# 3_-_STM32f4_debuger.net
KiCad netlist of a schematic drawn in Altium Designer
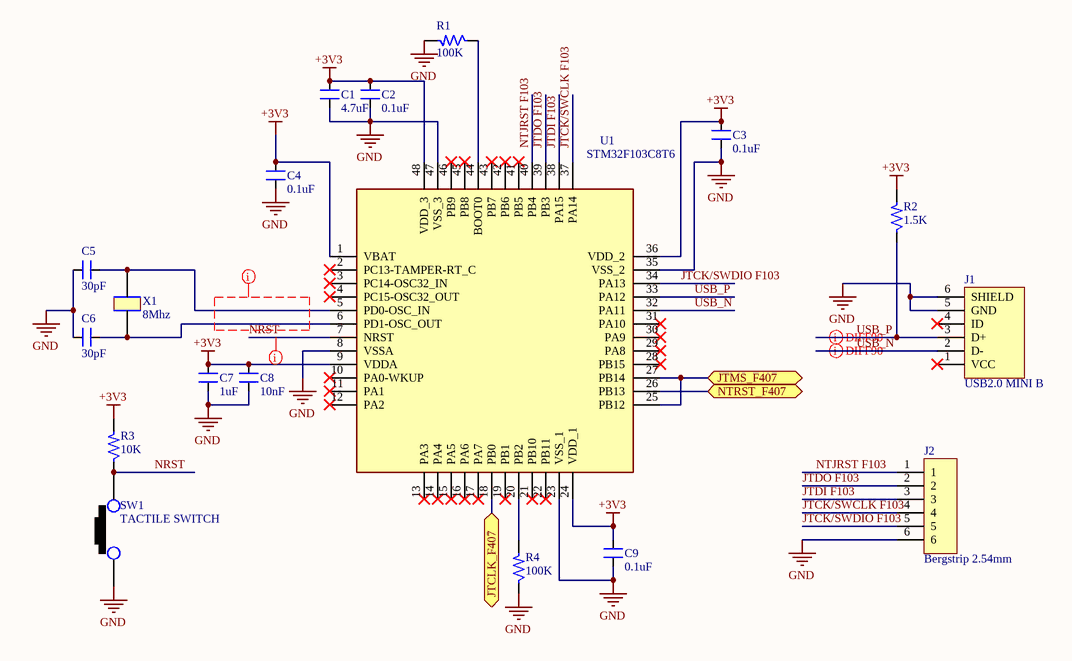
[diagram p0: [3]- STM32f4 debuger.SchDoc]

(export (version "E")
  (design (tool "Eeschema 10.0.6"))
  (components
    (comp (ref "C1")
      (value "4.7uF")
      (footprint "CAP_0805")
      (description "4.7µF ±10% 50V Ceramic Capacitor X5R 0805 (2012 Metric)")
      (fields
        (field (name "MANUFACTURER") "Yageo")
        (field (name "MANUFACTURER PART NUMBER") "GRM21BR61H475KE51L")
      )
      (libsource (lib "ESTEEMPCBLIB") (part "CAP_4.7uF-50V-10%-0805"))
    )
    (comp (ref "C2")
      (value "0.1uF")
      (footprint "CAP_0805")
      (description "0.1µF ±10% 50V Ceramic Capacitor X7R 0805 (2012 Metric)")
      (fields
        (field (name "MANUFACTURER") "Samsung")
        (field (name "MANUFACTURER PART NUMBER") "CL21B104KBCNNNC")
      )
      (libsource (lib "ESTEEMPCBLIB") (part "CAP_0.1uF-50V-10%-0805"))
    )
    (comp (ref "C3")
      (value "0.1uF")
      (footprint "CAP_0805")
      (description "0.1µF ±10% 50V Ceramic Capacitor X7R 0805 (2012 Metric)")
      (fields
        (field (name "MANUFACTURER") "Samsung")
        (field (name "MANUFACTURER PART NUMBER") "CL21B104KBCNNNC")
      )
      (libsource (lib "ESTEEMPCBLIB") (part "CAP_0.1uF-50V-10%-0805"))
    )
    (comp (ref "C4")
      (value "0.1uF")
      (footprint "CAP_0805")
      (description "0.1µF ±10% 50V Ceramic Capacitor X7R 0805 (2012 Metric)")
      (fields
        (field (name "MANUFACTURER") "Samsung")
        (field (name "MANUFACTURER PART NUMBER") "CL21B104KBCNNNC")
      )
      (libsource (lib "ESTEEMPCBLIB") (part "CAP_0.1uF-50V-10%-0805"))
    )
    (comp (ref "C5")
      (value "30pF")
      (footprint "CAP_0805")
      (description "±10% 50V Ceramic Capacitor C0G, NP0 0805 (2012 Metric)")
      (fields
        (field (name "MANUFACTURER PART NUMBER") "C0805C300K5GAC7800")
        (field (name "MANUFACTURER") "KEMET")
      )
      (libsource (lib "ESTEEMPCBLIB") (part "CAP_30pF-50V-10%-0805"))
    )
    (comp (ref "C6")
      (value "30pF")
      (footprint "CAP_0805")
      (description "±10% 50V Ceramic Capacitor C0G, NP0 0805 (2012 Metric)")
      (fields
        (field (name "MANUFACTURER PART NUMBER") "C0805C300K5GAC7800")
        (field (name "MANUFACTURER") "KEMET")
      )
      (libsource (lib "ESTEEMPCBLIB") (part "CAP_30pF-50V-10%-0805"))
    )
    (comp (ref "C7")
      (value "1uF")
      (footprint "CAP_0805")
      (description "1µF ±5% 50V Ceramic Capacitor X7R 0805 (2012 Metric)")
      (fields
        (field (name "MANUFACTURER") "Samsung")
        (field (name "MANUFACTURER PART NUMBER") "CC0805JKX7R9BB105")
      )
      (libsource (lib "ESTEEMPCBLIB") (part "CAP_1uF-50V-5%-0805"))
    )
    (comp (ref "C8")
      (value "10nF")
      (footprint "CAP_0805")
      (description "10000pF ±10% 50V Ceramic Capacitor X7R 0805 (2012 Metric)")
      (fields
        (field (name "MANUFACTURER") "Samsung")
        (field (name "MANUFACTURER PART NUMBER") "C0805C103K5RECAUTO")
      )
      (libsource (lib "ESTEEMPCBLIB") (part "CAP_10nF-50V-10%-0805"))
    )
    (comp (ref "C9")
      (value "0.1uF")
      (footprint "CAP_0805")
      (description "0.1µF ±10% 50V Ceramic Capacitor X7R 0805 (2012 Metric)")
      (fields
        (field (name "MANUFACTURER") "Samsung")
        (field (name "MANUFACTURER PART NUMBER") "CL21B104KBCNNNC")
      )
      (libsource (lib "ESTEEMPCBLIB") (part "CAP_0.1uF-50V-10%-0805"))
    )
    (comp (ref "J1")
      (value "USB2.0 MINI B")
      (footprint "CON_690-005-299-043")
      (description "USB - mini B USB 2.0 Receptacle Connector 5 Position Surface Mount, Right Angle")
      (fields
        (field (name "MANUFACTURER") "EDAC")
        (field (name "MANUFACTURER PART NUMBER") "690-005-299-043")
      )
      (libsource (lib "ESTEEMPCBLIB") (part "CON_USB2.0-MINIB-SMD"))
    )
    (comp (ref "J2")
      (value "Bergstrip 2.54mm")
      (footprint "CON6_100_59D78_TH_ST")
      (description "6 Pins, 1 Row 2.54mm Pitch, Straight bergstrip, Female")
      (fields (field (name "MANUFACTURER") "Molex") (field (name "MANUFACTURER PART NUMBER") "22-10-2061"))
      (libsource (lib "ESTEEMPCBLIB") (part "CON-BS-SKT_6X1-100-ST-TH"))
    )
    (comp (ref "R1")
      (value "100K")
      (footprint "RES_0603")
      (description "100 kOhms ±1% 0.1W, 1/10W Chip Resistor 0603 (1608 Metric) Automotive AEC-Q200 Thick Film")
      (fields
        (field (name "MANUFACTURER") "Stackpole Electronics")
        (field (name "MANUFACTURER PART NUMBER") "RMCF0603FT100K")
      )
      (libsource (lib "ESTEEMPCBLIB") (part "RES_100K-0.1W-1%-0603"))
    )
    (comp (ref "R2")
      (value "1.5K")
      (footprint "RES_0805")
      (description "1.5 kOhms ±1% 0.125W, 1/8W Chip Resistor 0805 (2012 Metric) Thick Film")
      (fields
        (field (name "MANUFACTURER") "TE Connectivity Passive Product")
        (field (name "MANUFACTURER PART NUMBER") "CRG0805F1K5")
      )
      (libsource (lib "ESTEEMPCBLIB") (part "RES_1.5K-0.125W-1%-0805"))
    )
    (comp (ref "R3")
      (value "10K")
      (footprint "RES_0603")
      (description "10 kOhms ±1% 0.1W, 1/10W Chip Resistor 0603 (1608 Metric) Automotive AEC-Q200 Thick Film")
      (fields (field (name "MANUFACTURER") "Walsin") (field (name "MANUFACTURER PART NUMBER") "WR06X1002FTL"))
      (libsource (lib "ESTEEMPCBLIB") (part "RES_10K-0.1W-1%-0603"))
    )
    (comp (ref "R4")
      (value "100K")
      (footprint "RES_0603")
      (description "100 kOhms ±1% 0.1W, 1/10W Chip Resistor 0603 (1608 Metric) Automotive AEC-Q200 Thick Film")
      (fields
        (field (name "MANUFACTURER") "Stackpole Electronics")
        (field (name "MANUFACTURER PART NUMBER") "RMCF0603FT100K")
      )
      (libsource (lib "ESTEEMPCBLIB") (part "RES_100K-0.1W-1%-0603"))
    )
    (comp (ref "SW1")
      (value "TACTILE SWITCH")
      (footprint "SW_342_SMD")
      (description "Tactile Switch SPST-NO Top Actuated Surface Mount")
      (fields
        (field (name "MANUFACTURER") "ITT C&K")
        (field (name "MANUFACTURER PART NUMBER") "RS-282G05A3-SMRT")
      )
      (libsource (lib "ESTEEMPCBLIB") (part "SW1_RS-282G05A3-SMRT-SMD"))
    )
    (comp (ref "U1")
      (value "STM32F103C8T6")
      (footprint "LQFP-48_19.6_393_58X11_SMD")
      (description "ARM® Cortex®-M3 STM32F1 Microcontroller IC 32-Bit 72MHz 64KB (64K x 8) FLASH 48-LQFP (7x7)")
      (fields (field (name "MANUFACTURER") "STMicroelectronics"))
      (libsource (lib "ESTEEMPCBLIB") (part "IC_STM32F103C8T6"))
    )
    (comp (ref "X1")
      (value "8Mhz")
      (footprint "XTAL_314_240X47_SMD")
      (description "8MHz ±30ppm Crystal 32pF 60 Ohms HC-49/US")
      (fields
        (field (name "MANUFACTURER") "Fox Electronics")
        (field (name "MANUFACTURER PART NUMBER") "ECS-80-32-5PX-TR")
      )
      (libsource (lib "ESTEEMPCBLIB") (part "XTAL_8MHZ-ECS-80-32-5PX-SMD"))
    )
  )
  (nets
    (net (code "1") (name "+3V3") (class "Default")
      (node (ref "C1") (pin "2") (pinfunction "2_2") (pintype "passive"))
      (node (ref "C2") (pin "2") (pinfunction "2_2") (pintype "passive"))
      (node (ref "C3") (pin "2") (pinfunction "2_2") (pintype "passive"))
      (node (ref "C4") (pin "2") (pinfunction "2_2") (pintype "passive"))
      (node (ref "C7") (pin "2") (pinfunction "2_2") (pintype "passive"))
      (node (ref "C8") (pin "2") (pinfunction "2_2") (pintype "passive"))
      (node (ref "C9") (pin "2") (pinfunction "2_2") (pintype "passive"))
      (node (ref "R2") (pin "2") (pinfunction "2_2") (pintype "passive"))
      (node (ref "R3") (pin "2") (pinfunction "2_2") (pintype "passive"))
      (node (ref "U1") (pin "1") (pinfunction "VBAT_1") (pintype "passive"))
      (node (ref "U1") (pin "24") (pinfunction "VDD_1_24") (pintype "passive"))
      (node (ref "U1") (pin "36") (pinfunction "VDD_2_36") (pintype "passive"))
      (node (ref "U1") (pin "48") (pinfunction "VDD_3_48") (pintype "passive"))
      (node (ref "U1") (pin "9") (pinfunction "VDDA_9") (pintype "passive"))
    )
    (net (code "2") (name "/JTCK{slash}SWCLK F103") (class "Default")
      (node (ref "J2") (pin "4") (pinfunction "4_4") (pintype "passive"))
      (node (ref "U1") (pin "37") (pinfunction "PA14_37") (pintype "passive"))
    )
    (net (code "3") (name "/JTCK{slash}SWDIO F103") (class "Default")
      (node (ref "J2") (pin "5") (pinfunction "5_5") (pintype "passive"))
      (node (ref "U1") (pin "34") (pinfunction "PA13_34") (pintype "passive"))
    )
    (net (code "4") (name "/JTCLK_F407") (class "Default")
      (node (ref "U1") (pin "18") (pinfunction "PB0_18") (pintype "passive"))
    )
    (net (code "5") (name "/JTDI F103") (class "Default")
      (node (ref "J2") (pin "3") (pinfunction "3_3") (pintype "passive"))
      (node (ref "U1") (pin "38") (pinfunction "PA15_38") (pintype "passive"))
    )
    (net (code "6") (name "/JTDO F103") (class "Default")
      (node (ref "J2") (pin "2") (pinfunction "2_2") (pintype "passive"))
      (node (ref "U1") (pin "39") (pinfunction "PB3_39") (pintype "passive"))
    )
    (net (code "7") (name "/JTMS_F407") (class "Default")
      (node (ref "U1") (pin "25") (pinfunction "PB12_25") (pintype "passive"))
      (node (ref "U1") (pin "27") (pinfunction "PB14_27") (pintype "passive"))
    )
    (net (code "8") (name "/NRST") (class "Default")
      (node (ref "R3") (pin "1") (pinfunction "1_1") (pintype "passive"))
      (node (ref "SW1") (pin "2") (pinfunction "2_2") (pintype "passive"))
      (node (ref "U1") (pin "7") (pinfunction "NRST_7") (pintype "passive"))
    )
    (net (code "9") (name "/NTJRST F103") (class "Default")
      (node (ref "J2") (pin "1") (pinfunction "1_1") (pintype "passive"))
      (node (ref "U1") (pin "40") (pinfunction "PB4_40") (pintype "passive"))
    )
    (net (code "10") (name "/NTRST_F407") (class "Default")
      (node (ref "U1") (pin "26") (pinfunction "PB13_26") (pintype "passive"))
    )
    (net (code "11") (name "/USB_N") (class "Default")
      (node (ref "J1") (pin "2") (pinfunction "D-_2") (pintype "passive"))
      (node (ref "U1") (pin "32") (pinfunction "PA11_32") (pintype "passive"))
    )
    (net (code "12") (name "/USB_P") (class "Default")
      (node (ref "J1") (pin "3") (pinfunction "D+_3") (pintype "passive"))
      (node (ref "R2") (pin "1") (pinfunction "1_1") (pintype "passive"))
      (node (ref "U1") (pin "33") (pinfunction "PA12_33") (pintype "passive"))
    )
    (net (code "13") (name "GND") (class "Default")
      (node (ref "C1") (pin "1") (pinfunction "1_1") (pintype "passive"))
      (node (ref "C2") (pin "1") (pinfunction "1_1") (pintype "passive"))
      (node (ref "C3") (pin "1") (pinfunction "1_1") (pintype "passive"))
      (node (ref "C4") (pin "1") (pinfunction "1_1") (pintype "passive"))
      (node (ref "C5") (pin "1") (pinfunction "1_1") (pintype "passive"))
      (node (ref "C6") (pin "1") (pinfunction "1_1") (pintype "passive"))
      (node (ref "C7") (pin "1") (pinfunction "1_1") (pintype "passive"))
      (node (ref "C8") (pin "1") (pinfunction "1_1") (pintype "passive"))
      (node (ref "C9") (pin "1") (pinfunction "1_1") (pintype "passive"))
      (node (ref "J1") (pin "5") (pinfunction "GND_5") (pintype "passive"))
      (node (ref "J1") (pin "6") (pinfunction "SHIELD_6") (pintype "passive"))
      (node (ref "J2") (pin "6") (pinfunction "6_6") (pintype "passive"))
      (node (ref "R1") (pin "2") (pinfunction "2_2") (pintype "passive"))
      (node (ref "R4") (pin "1") (pinfunction "1_1") (pintype "passive"))
      (node (ref "SW1") (pin "1") (pinfunction "1_1") (pintype "passive"))
      (node (ref "U1") (pin "23") (pinfunction "VSS_1_23") (pintype "passive"))
      (node (ref "U1") (pin "35") (pinfunction "VSS_2_35") (pintype "passive"))
      (node (ref "U1") (pin "47") (pinfunction "VSS_3_47") (pintype "passive"))
      (node (ref "U1") (pin "8") (pinfunction "VSSA_8") (pintype "passive"))
    )
    (net (code "14") (name "Net-(U1-BOOT0)") (class "Default")
      (node (ref "R1") (pin "1") (pinfunction "1_1") (pintype "passive"))
      (node (ref "U1") (pin "44") (pinfunction "BOOT0_44") (pintype "passive"))
    )
    (net (code "15") (name "Net-(U1-PB2)") (class "Default")
      (node (ref "R4") (pin "2") (pinfunction "2_2") (pintype "passive"))
      (node (ref "U1") (pin "20") (pinfunction "PB2_20") (pintype "passive"))
    )
    (net (code "16") (name "Net-(U1-PD0-OSC_IN)") (class "Default")
      (node (ref "C5") (pin "2") (pinfunction "2_2") (pintype "passive"))
      (node (ref "U1") (pin "5") (pinfunction "PD0-OSC_IN_5") (pintype "passive"))
      (node (ref "X1") (pin "2") (pinfunction "2_2") (pintype "passive"))
    )
    (net (code "17") (name "Net-(U1-PD1-OSC_OUT)") (class "Default")
      (node (ref "C6") (pin "2") (pinfunction "2_2") (pintype "passive"))
      (node (ref "U1") (pin "6") (pinfunction "PD1-OSC_OUT_6") (pintype "passive"))
      (node (ref "X1") (pin "1") (pinfunction "1_1") (pintype "passive"))
    )
    (net (code "18") (name "unconnected-(J1-ID-Pad4)") (class "Default")
      (node (ref "J1") (pin "4") (pinfunction "ID_4") (pintype "passive+no_connect"))
    )
    (net (code "19") (name "unconnected-(J1-VCC-Pad1)") (class "Default")
      (node (ref "J1") (pin "1") (pinfunction "VCC_1") (pintype "passive+no_connect"))
    )
    (net (code "20") (name "unconnected-(U1-PA0-WKUP-Pad10)") (class "Default")
      (node (ref "U1") (pin "10") (pinfunction "PA0-WKUP_10") (pintype "passive+no_connect"))
    )
    (net (code "21") (name "unconnected-(U1-PA1-Pad11)") (class "Default")
      (node (ref "U1") (pin "11") (pinfunction "PA1_11") (pintype "passive+no_connect"))
    )
    (net (code "22") (name "unconnected-(U1-PA2-Pad12)") (class "Default")
      (node (ref "U1") (pin "12") (pinfunction "PA2_12") (pintype "passive+no_connect"))
    )
    (net (code "23") (name "unconnected-(U1-PA3-Pad13)") (class "Default")
      (node (ref "U1") (pin "13") (pinfunction "PA3_13") (pintype "passive+no_connect"))
    )
    (net (code "24") (name "unconnected-(U1-PA4-Pad14)") (class "Default")
      (node (ref "U1") (pin "14") (pinfunction "PA4_14") (pintype "passive+no_connect"))
    )
    (net (code "25") (name "unconnected-(U1-PA5-Pad15)") (class "Default")
      (node (ref "U1") (pin "15") (pinfunction "PA5_15") (pintype "passive+no_connect"))
    )
    (net (code "26") (name "unconnected-(U1-PA6-Pad16)") (class "Default")
      (node (ref "U1") (pin "16") (pinfunction "PA6_16") (pintype "passive+no_connect"))
    )
    (net (code "27") (name "unconnected-(U1-PA7-Pad17)") (class "Default")
      (node (ref "U1") (pin "17") (pinfunction "PA7_17") (pintype "passive+no_connect"))
    )
    (net (code "28") (name "unconnected-(U1-PA8-Pad29)") (class "Default")
      (node (ref "U1") (pin "29") (pinfunction "PA8_29") (pintype "passive+no_connect"))
    )
    (net (code "29") (name "unconnected-(U1-PA9-Pad30)") (class "Default")
      (node (ref "U1") (pin "30") (pinfunction "PA9_30") (pintype "passive+no_connect"))
    )
    (net (code "30") (name "unconnected-(U1-PA10-Pad31)") (class "Default")
      (node (ref "U1") (pin "31") (pinfunction "PA10_31") (pintype "passive+no_connect"))
    )
    (net (code "31") (name "unconnected-(U1-PB1-Pad19)") (class "Default")
      (node (ref "U1") (pin "19") (pinfunction "PB1_19") (pintype "passive+no_connect"))
    )
    (net (code "32") (name "unconnected-(U1-PB5-Pad41)") (class "Default")
      (node (ref "U1") (pin "41") (pinfunction "PB5_41") (pintype "passive+no_connect"))
    )
    (net (code "33") (name "unconnected-(U1-PB6-Pad42)") (class "Default")
      (node (ref "U1") (pin "42") (pinfunction "PB6_42") (pintype "passive+no_connect"))
    )
    (net (code "34") (name "unconnected-(U1-PB7-Pad43)") (class "Default")
      (node (ref "U1") (pin "43") (pinfunction "PB7_43") (pintype "passive+no_connect"))
    )
    (net (code "35") (name "unconnected-(U1-PB8-Pad45)") (class "Default")
      (node (ref "U1") (pin "45") (pinfunction "PB8_45") (pintype "passive+no_connect"))
    )
    (net (code "36") (name "unconnected-(U1-PB9-Pad46)") (class "Default")
      (node (ref "U1") (pin "46") (pinfunction "PB9_46") (pintype "passive+no_connect"))
    )
    (net (code "37") (name "unconnected-(U1-PB10-Pad21)") (class "Default")
      (node (ref "U1") (pin "21") (pinfunction "PB10_21") (pintype "passive+no_connect"))
    )
    (net (code "38") (name "unconnected-(U1-PB11-Pad22)") (class "Default")
      (node (ref "U1") (pin "22") (pinfunction "PB11_22") (pintype "passive+no_connect"))
    )
    (net (code "39") (name "unconnected-(U1-PB15-Pad28)") (class "Default")
      (node (ref "U1") (pin "28") (pinfunction "PB15_28") (pintype "passive+no_connect"))
    )
    (net (code "40") (name "unconnected-(U1-PC13-TAMPER-RT_C-Pad2)") (class "Default")
      (node (ref "U1") (pin "2") (pinfunction "PC13-TAMPER-RT_C_2") (pintype "passive+no_connect"))
    )
    (net (code "41") (name "unconnected-(U1-PC14-OSC32_IN-Pad3)") (class "Default")
      (node (ref "U1") (pin "3") (pinfunction "PC14-OSC32_IN_3") (pintype "passive+no_connect"))
    )
    (net (code "42") (name "unconnected-(U1-PC15-OSC32_OUT-Pad4)") (class "Default")
      (node (ref "U1") (pin "4") (pinfunction "PC15-OSC32_OUT_4") (pintype "passive+no_connect"))
    )
  )
)
